# ESP_Grow_Main_Rev_A.net
KiCad netlist of a schematic drawn in Altium Designer
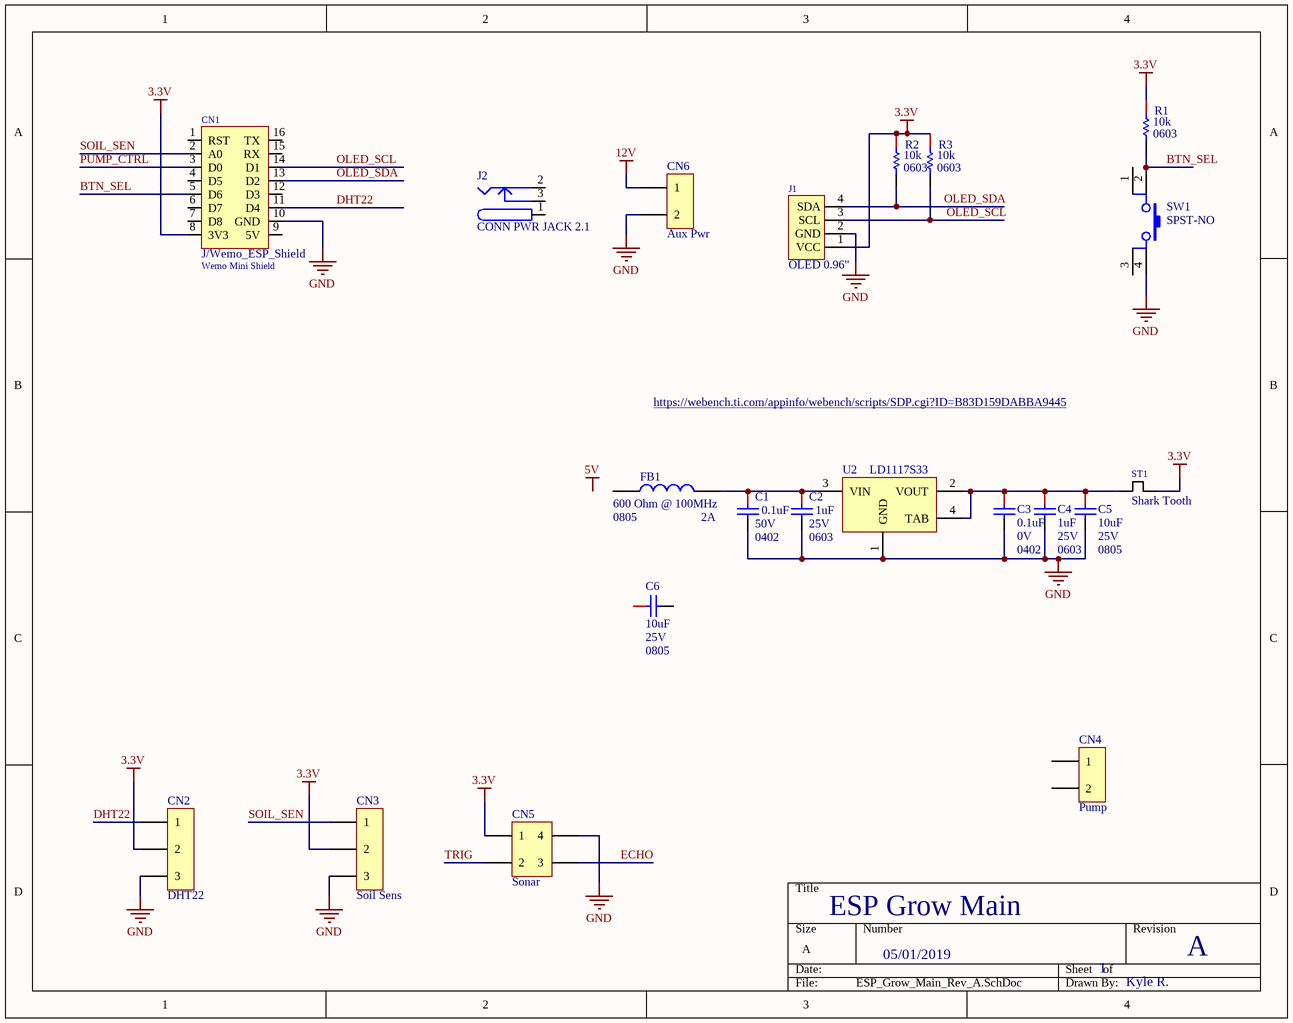
[diagram p0: ESP_Grow_Main_Rev_A.SchDoc]

(export (version "E")
  (design (tool "Eeschema 10.0.6"))
  (components
    (comp (ref "C1")
      (value "0.1uF")
      (footprint "CAPC0402(1005)_M")
      (description "CAP CER 0.1UF 50V X7R 0402")
      (fields
        (field (name "VOLTAGE (RATED)") "50V")
        (field (name "PACKAGE (IMPERIAL)") "0402")
        (field (name "TOLERANCE") "20%")
      )
      (libsource (lib "OLogic Nexus Vault") (part "=Capacitance"))
    )
    (comp (ref "C2")
      (value "1uF")
      (footprint "CAPC0603(1608)_N")
      (description "CAP CER 1UF 25V 10% X7R 0603")
      (fields
        (field (name "VOLTAGE (RATED)") "25V")
        (field (name "PACKAGE (IMPERIAL)") "0603")
        (field (name "TOLERANCE") "10%")
      )
      (libsource (lib "OLogic Nexus Vault") (part "=Capacitance"))
    )
    (comp (ref "C3")
      (value "0.1uF")
      (footprint "CAPC0402(1005)_M")
      (description "CAP CER 0.1UF 50V X7R 0402")
      (fields
        (field (name "VOLTAGE (RATED)") "0V")
        (field (name "PACKAGE (IMPERIAL)") "0402")
        (field (name "TOLERANCE") "20%")
      )
      (libsource (lib "OLogic Nexus Vault") (part "=Capacitance"))
    )
    (comp (ref "C4")
      (value "1uF")
      (footprint "CAPC0603(1608)_N")
      (description "CAP CER 1UF 25V 10% X7R 0603")
      (fields
        (field (name "VOLTAGE (RATED)") "25V")
        (field (name "PACKAGE (IMPERIAL)") "0603")
        (field (name "TOLERANCE") "10%")
      )
      (libsource (lib "OLogic Nexus Vault") (part "=Capacitance"))
    )
    (comp (ref "C5")
      (value "10uF")
      (footprint "CAPC0805(2012)_L")
      (description "CAP CER 10UF 25V X6S 0805")
      (fields
        (field (name "VOLTAGE (RATED)") "25V")
        (field (name "PACKAGE (IMPERIAL)") "0805")
        (field (name "TOLERANCE") "20%")
      )
      (libsource (lib "OLogic Nexus Vault") (part "=Capacitance"))
    )
    (comp (ref "C6")
      (value "10uF")
      (footprint "CAPC0805(2012)_L")
      (description "CAP CER 10UF 25V X6S 0805")
      (fields
        (field (name "VOLTAGE (RATED)") "25V")
        (field (name "PACKAGE (IMPERIAL)") "0805")
        (field (name "TOLERANCE") "20%")
      )
      (libsource (lib "OLogic Nexus Vault") (part "=Capacitance"))
    )
    (comp (ref "CN1")
      (value "J/Wemo_ESP_Shield")
      (footprint "Wemos_d1")
      (description "Wemo Mini Shield for ESP-12")
      (fields (field (name "NAME") "Wemo Mini Shield"))
      (libsource (lib "Kyle_Lib_04-20-19") (part "J/Wemo_ESP_Shield"))
    )
    (comp (ref "CN2")
      (value "DHT22")
      (footprint "Molex 1x3 Microfit 90deg")
      (description "Molex Microfit 1x3 90deg Header")
      (fields
        (field (name "MANUFACTURER") "Molex Inc")
        (field (name "MANUFACTURER PART NUMBER") "0436500304")
      )
      (libsource (lib "ologic-library_2018-09-22") (part "CMP-001-0428-01"))
    )
    (comp (ref "CN3")
      (value "Soil Sens")
      (footprint "Molex 1x3 Microfit 90deg")
      (description "Molex Microfit 1x3 90deg Header")
      (fields
        (field (name "MANUFACTURER") "Molex Inc")
        (field (name "MANUFACTURER PART NUMBER") "0436500304")
      )
      (libsource (lib "ologic-library_2018-09-22") (part "CMP-001-0428-01"))
    )
    (comp (ref "CN4")
      (value "Pump")
      (footprint "Molex 1x2 Microfit 90deg")
      (description "Molex Microfit 1x2 90deg Header")
      (fields (field (name "MANUFACTURER") "Molex") (field (name "MANUFACTURER PART NUMBER") "43650-0204"))
      (libsource (lib "ologic-library_2018-09-22") (part "CMP-001-0425-01"))
    )
    (comp (ref "CN5")
      (value "Sonar")
      (footprint "Molex 2x2 Microfit 90deg")
      (description "Molex Microfit 2x2 90deg Header")
      (fields
        (field (name "MANUFACTURER") "Molex Inc")
        (field (name "MANUFACTURER PART NUMBER") "0430450400")
      )
      (libsource (lib "ologic-library_2018-09-22") (part "CMP-001-0429-01"))
    )
    (comp (ref "CN6")
      (value "Aux Pwr")
      (footprint "Molex 1x2 Microfit 3.0")
      (description "Molex Microfit 1x2 Vert Header")
      (fields
        (field (name "MANUFACTURER PART NUMBER") "0430450227")
        (field (name "MANUFACTURER") "Molex, LLC")
      )
      (libsource (lib "OLogic Nexus Vault") (part "MICROFIT 3.0 HDR VERT CPI 2CKT"))
    )
    (comp (ref "FB1")
      (value "FERRITE 600 OHM 2.0A 0805")
      (footprint "RESC0805(2012)_N")
      (description "600 OHM 0805 2.0A")
      (fields
        (field (name "MANUFACTURER PART NUMBER") "742792040")
        (field (name "IMPEDANCE @ FREQUENCY") "600 Ohm @ 100MHz")
        (field (name "PACKAGE / CASE") "0805")
        (field (name "MANUFACTURER") "Wurth Electronics Inc")
        (field (name "CURRENT RATING") "2A")
        (field (name "CREATOR") "osman")
      )
      (libsource (lib "OLogic Nexus Vault") (part "FERRITE 600 OHM 2.0A 0805"))
    )
    (comp (ref "J1")
      (value "OLED 0.96\"")
      (footprint "OLED_0.96_I2C")
      (description "SSD1306 I2C OLED 0.96\"")
      (libsource (lib "Kyle_Lib_04-20-19") (part "OLED_0.96_I2C"))
    )
    (comp (ref "J2")
      (value "CONN PWR JACK 2.1")
      (footprint "CONN_PWR_JACK_2.1x5.5mm")
      (description "2.1 mm barrel jack")
      (fields
        (field (name "MANUFACTURER PART NUMBER") "PJ-002A")
        (field (name "MANUFACTURER") "CUI Inc")
        (field (name "PUBLISHER") "Altium Limited")
      )
      (libsource (lib "OLogic Nexus Vault") (part "CONN PWR JACK 2.1"))
    )
    (comp (ref "R1")
      (value "10K")
      (footprint "RESC0603(1608)_M")
      (description "RES 10K OHM 1/10W 1% 0603 SMD")
      (fields
        (field (name "PACKAGE (IMPERIAL)") "0603")
        (field (name "RESISTANCE") "10k")
        (field (name "POWER") "100mW")
        (field (name "TOLERANCE") "1%")
      )
      (libsource (lib "OLogic Nexus Vault") (part "=Resistance"))
    )
    (comp (ref "R2")
      (value "10K")
      (footprint "RESC0603(1608)_M")
      (description "RES 10K OHM 1/10W 1% 0603 SMD")
      (fields
        (field (name "PACKAGE (IMPERIAL)") "0603")
        (field (name "RESISTANCE") "10k")
        (field (name "POWER") "100mW")
        (field (name "TOLERANCE") "1%")
      )
      (libsource (lib "OLogic Nexus Vault") (part "=Resistance"))
    )
    (comp (ref "R3")
      (value "10K")
      (footprint "RESC0603(1608)_M")
      (description "RES 10K OHM 1/10W 1% 0603 SMD")
      (fields
        (field (name "PACKAGE (IMPERIAL)") "0603")
        (field (name "RESISTANCE") "10k")
        (field (name "POWER") "100mW")
        (field (name "TOLERANCE") "1%")
      )
      (libsource (lib "OLogic Nexus Vault") (part "=Resistance"))
    )
    (comp (ref "ST1")
      (value "Shark Tooth")
      (footprint "SharkTooth")
      (description "Sharks Tooth Small")
      (libsource (lib "Kyle_Lib_04-20-19") (part "Shark Tooth"))
    )
    (comp (ref "SW1")
      (value "PTS645SM43SMTR92 LFS")
      (footprint "SW TACT Red 6mm x 6mm")
      (description "SWITCH TACTILE SPST-NO 0.05A 12V")
      (fields (field (name "CIRCUIT") "SPST-NO") (field (name "MANUFACTURER") "C&K"))
      (libsource (lib "OLogic Nexus Vault") (part "PTS645SM43SMTR92 LFS"))
    )
    (comp (ref "U2")
      (value "LD1117S33")
      (footprint "DSO-G3")
      (description "3.3 volt fixed regulator, 800mA")
      (libsource (lib "OLogic Nexus Vault") (part "LD1117S33"))
    )
  )
  (nets
    (net (code "1") (name "/BTN_SEL") (class "Default")
      (node (ref "CN1") (pin "5") (pinfunction "D6_5") (pintype "power_in"))
      (node (ref "R1") (pin "2") (pinfunction "2_2") (pintype "passive"))
      (node (ref "SW1") (pin "2") (pinfunction "2_2") (pintype "passive"))
    )
    (net (code "2") (name "/DHT22") (class "Default")
      (node (ref "CN1") (pin "11") (pinfunction "D4_11") (pintype "power_in"))
      (node (ref "CN2") (pin "1") (pinfunction "1_1") (pintype "passive"))
    )
    (net (code "3") (name "/ECHO") (class "Default")
      (node (ref "CN5") (pin "3") (pinfunction "3_3") (pintype "passive"))
    )
    (net (code "4") (name "/OLED_SCL") (class "Default")
      (node (ref "CN1") (pin "14") (pinfunction "D1_14") (pintype "power_in"))
      (node (ref "J1") (pin "3") (pinfunction "SCL_3") (pintype "passive"))
      (node (ref "R3") (pin "2") (pinfunction "2_2") (pintype "passive"))
    )
    (net (code "5") (name "/OLED_SDA") (class "Default")
      (node (ref "CN1") (pin "13") (pinfunction "D2_13") (pintype "power_in"))
      (node (ref "J1") (pin "4") (pinfunction "SDA_4") (pintype "passive"))
      (node (ref "R2") (pin "2") (pinfunction "2_2") (pintype "passive"))
    )
    (net (code "6") (name "/PUMP_CTRL") (class "Default")
      (node (ref "CN1") (pin "3") (pinfunction "D0_3") (pintype "power_in"))
    )
    (net (code "7") (name "/SOIL_SEN") (class "Default")
      (node (ref "CN1") (pin "2") (pinfunction "A0_2") (pintype "power_in"))
      (node (ref "CN3") (pin "1") (pinfunction "1_1") (pintype "passive"))
    )
    (net (code "8") (name "/TRIG") (class "Default")
      (node (ref "CN5") (pin "2") (pinfunction "2_2") (pintype "passive"))
    )
    (net (code "9") (name "3.3V") (class "Default")
      (node (ref "CN1") (pin "8") (pinfunction "3V3_8") (pintype "power_in"))
      (node (ref "CN2") (pin "2") (pinfunction "2_2") (pintype "passive"))
      (node (ref "CN3") (pin "2") (pinfunction "2_2") (pintype "passive"))
      (node (ref "CN5") (pin "1") (pinfunction "1_1") (pintype "passive"))
      (node (ref "J1") (pin "1") (pinfunction "VCC_1") (pintype "passive"))
      (node (ref "R1") (pin "1") (pinfunction "1_1") (pintype "passive"))
      (node (ref "R2") (pin "1") (pinfunction "1_1") (pintype "passive"))
      (node (ref "R3") (pin "1") (pinfunction "1_1") (pintype "passive"))
      (node (ref "ST1") (pin "2") (pinfunction "2_2") (pintype "power_in"))
    )
    (net (code "11") (name "12V") (class "Default")
      (node (ref "CN6") (pin "1") (pinfunction "1_1") (pintype "passive"))
    )
    (net (code "12") (name "GND") (class "Default")
      (node (ref "C1") (pin "2") (pinfunction "2_2") (pintype "passive"))
      (node (ref "C2") (pin "2") (pinfunction "2_2") (pintype "passive"))
      (node (ref "C3") (pin "2") (pinfunction "2_2") (pintype "passive"))
      (node (ref "C4") (pin "2") (pinfunction "2_2") (pintype "passive"))
      (node (ref "C5") (pin "2") (pinfunction "2_2") (pintype "passive"))
      (node (ref "CN1") (pin "10") (pinfunction "GND_10") (pintype "power_in"))
      (node (ref "CN2") (pin "3") (pinfunction "3_3") (pintype "passive"))
      (node (ref "CN3") (pin "3") (pinfunction "3_3") (pintype "passive"))
      (node (ref "CN5") (pin "4") (pinfunction "4_4") (pintype "passive"))
      (node (ref "CN6") (pin "2") (pinfunction "2_2") (pintype "passive"))
      (node (ref "J1") (pin "2") (pinfunction "GND_2") (pintype "passive"))
      (node (ref "SW1") (pin "4") (pinfunction "4_4") (pintype "passive"))
      (node (ref "U2") (pin "1") (pinfunction "GND_1") (pintype "power_in"))
    )
    (net (code "13") (name "Net-(U2-TAB)") (class "Default")
      (node (ref "C3") (pin "1") (pinfunction "1_1") (pintype "passive"))
      (node (ref "C4") (pin "1") (pinfunction "1_1") (pintype "passive"))
      (node (ref "C5") (pin "1") (pinfunction "1_1") (pintype "passive"))
      (node (ref "ST1") (pin "1") (pinfunction "1_1") (pintype "power_in"))
      (node (ref "U2") (pin "2") (pinfunction "VOUT_2") (pintype "power_in"))
      (node (ref "U2") (pin "4") (pinfunction "TAB_4") (pintype "power_in"))
    )
    (net (code "14") (name "Net-(U2-VIN)") (class "Default")
      (node (ref "C1") (pin "1") (pinfunction "1_1") (pintype "passive"))
      (node (ref "C2") (pin "1") (pinfunction "1_1") (pintype "passive"))
      (node (ref "FB1") (pin "2") (pinfunction "2_2") (pintype "passive"))
      (node (ref "U2") (pin "3") (pinfunction "VIN_3") (pintype "power_in"))
    )
    (net (code "15") (name "unconnected-(C6-Pad1)") (class "Default")
      (node (ref "C6") (pin "1") (pinfunction "1_1") (pintype "passive"))
    )
    (net (code "16") (name "unconnected-(C6-Pad2)") (class "Default")
      (node (ref "C6") (pin "2") (pinfunction "2_2") (pintype "passive"))
    )
    (net (code "17") (name "unconnected-(CN1-5V-Pad9)") (class "Default")
      (node (ref "CN1") (pin "9") (pinfunction "5V_9") (pintype "power_in"))
    )
    (net (code "18") (name "unconnected-(CN1-D3-Pad12)") (class "Default")
      (node (ref "CN1") (pin "12") (pinfunction "D3_12") (pintype "power_in"))
    )
    (net (code "19") (name "unconnected-(CN1-D5-Pad4)") (class "Default")
      (node (ref "CN1") (pin "4") (pinfunction "D5_4") (pintype "power_in"))
    )
    (net (code "20") (name "unconnected-(CN1-D7-Pad6)") (class "Default")
      (node (ref "CN1") (pin "6") (pinfunction "D7_6") (pintype "power_in"))
    )
    (net (code "21") (name "unconnected-(CN1-D8-Pad7)") (class "Default")
      (node (ref "CN1") (pin "7") (pinfunction "D8_7") (pintype "power_in"))
    )
    (net (code "22") (name "unconnected-(CN1-RST-Pad1)") (class "Default")
      (node (ref "CN1") (pin "1") (pinfunction "RST_1") (pintype "power_in"))
    )
    (net (code "23") (name "unconnected-(CN1-RX-Pad15)") (class "Default")
      (node (ref "CN1") (pin "15") (pinfunction "RX_15") (pintype "power_in"))
    )
    (net (code "24") (name "unconnected-(CN1-TX-Pad16)") (class "Default")
      (node (ref "CN1") (pin "16") (pinfunction "TX_16") (pintype "power_in"))
    )
    (net (code "25") (name "unconnected-(CN4-Pad1)") (class "Default")
      (node (ref "CN4") (pin "1") (pinfunction "1_1") (pintype "passive"))
    )
    (net (code "26") (name "unconnected-(CN4-Pad2)") (class "Default")
      (node (ref "CN4") (pin "2") (pinfunction "2_2") (pintype "passive"))
    )
    (net (code "27") (name "unconnected-(FB1-Pad1)") (class "Default")
      (node (ref "FB1") (pin "1") (pinfunction "1_1") (pintype "passive"))
    )
    (net (code "28") (name "unconnected-(J2-Pad1)") (class "Default")
      (node (ref "J2") (pin "1") (pinfunction "1_1") (pintype "power_in"))
    )
    (net (code "29") (name "unconnected-(J2-Pad2)") (class "Default")
      (node (ref "J2") (pin "2") (pinfunction "2_2") (pintype "power_in"))
    )
    (net (code "30") (name "unconnected-(J2-Pad3)") (class "Default")
      (node (ref "J2") (pin "3") (pinfunction "3_3") (pintype "power_in"))
    )
    (net (code "31") (name "unconnected-(SW1-Pad1)") (class "Default")
      (node (ref "SW1") (pin "1") (pinfunction "1_1") (pintype "passive"))
    )
    (net (code "32") (name "unconnected-(SW1-Pad3)") (class "Default")
      (node (ref "SW1") (pin "3") (pinfunction "3_3") (pintype "passive"))
    )
  )
)
